# B113X.net
KiCad netlist of a schematic drawn in EAGLE
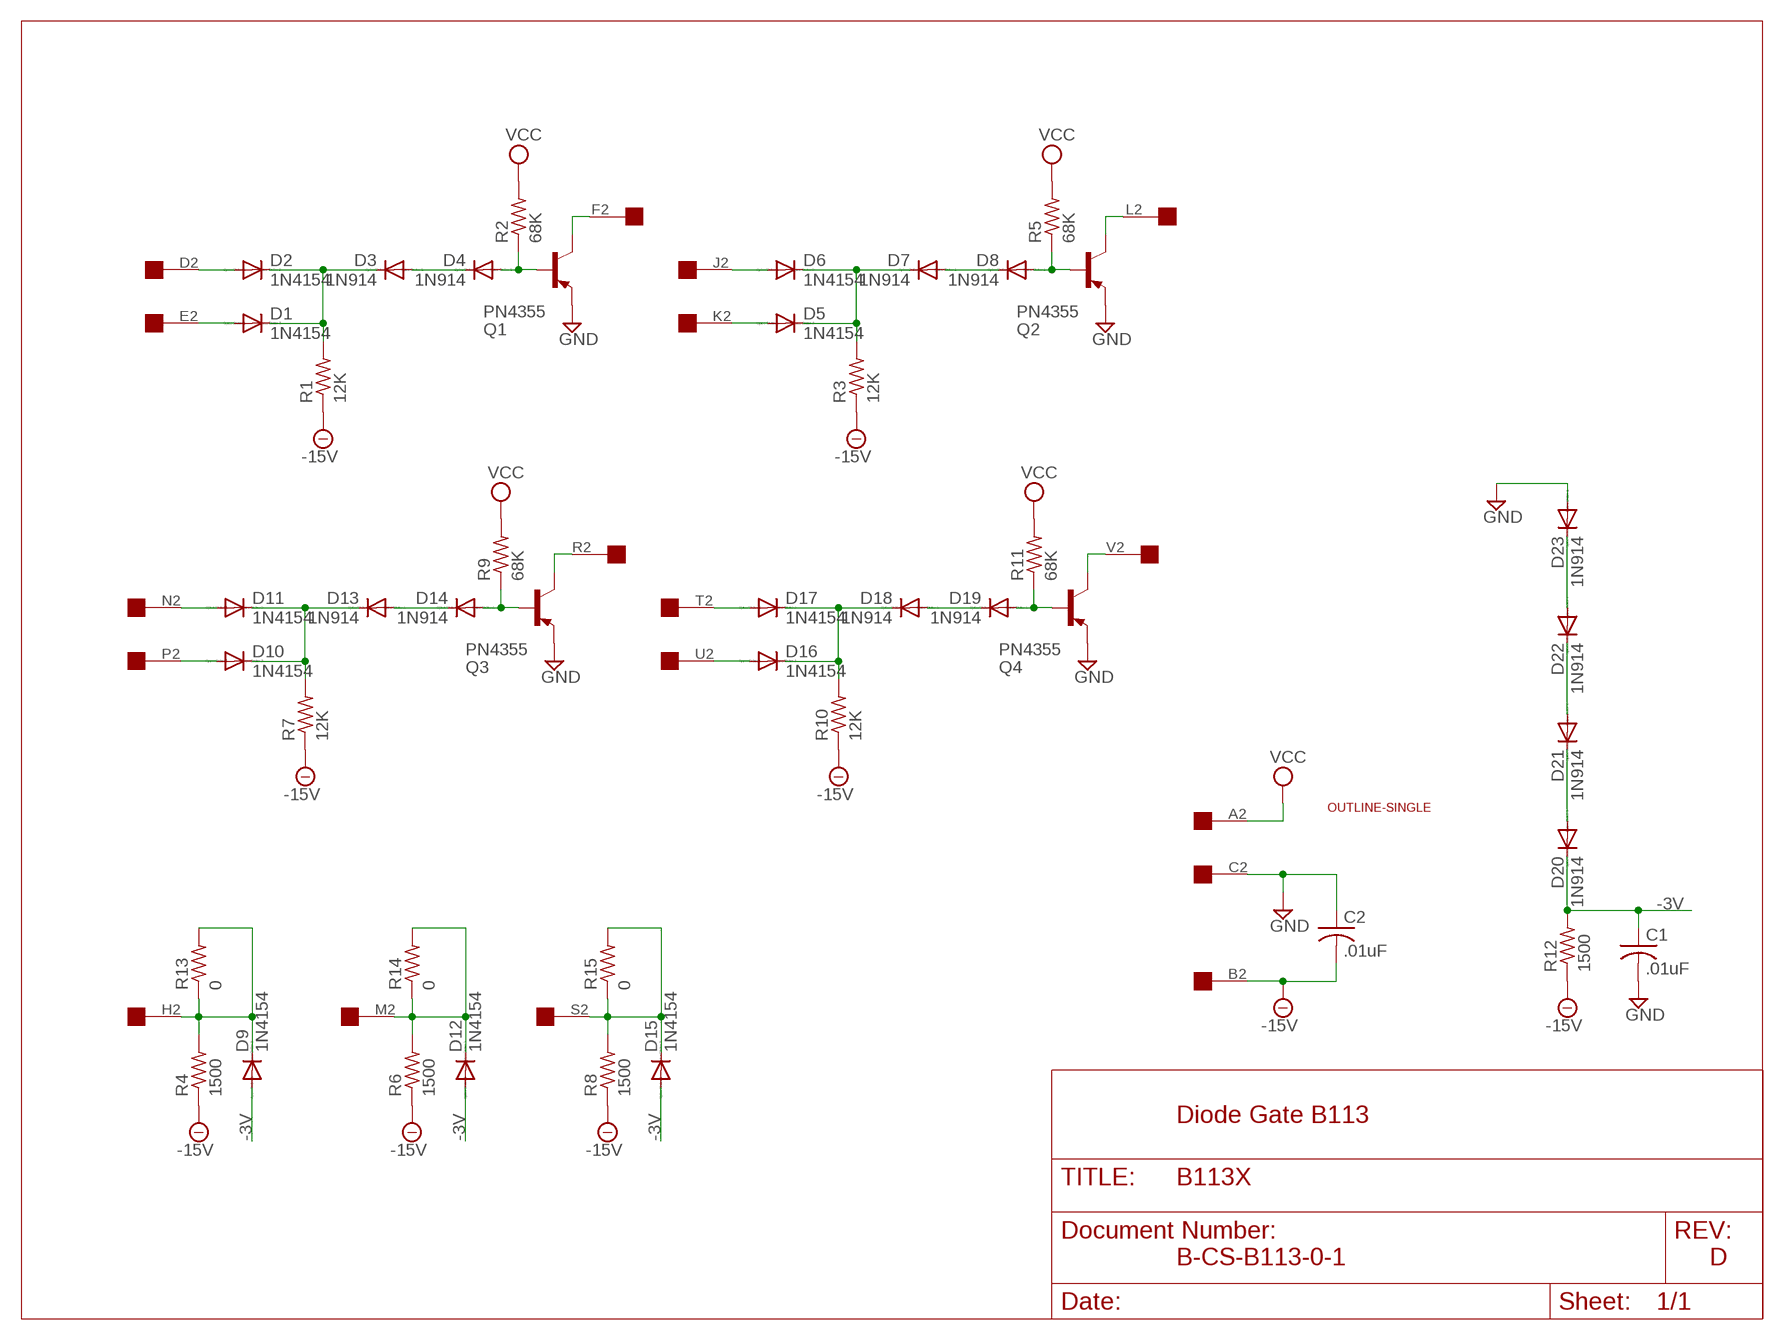
[diagram p0: schematic, sheet 1]

(export (version "E")
  (design (tool "Eeschema 10.0.6"))
  (components
    (comp (ref "C1")
      (value ".01uF")
      (footprint "eagle-import:C063-025X075")
      (libsource (lib "eagle-import") (part "C-US"))
    )
    (comp (ref "C2")
      (value ".01uF")
      (footprint "eagle-import:C063-025X075")
      (libsource (lib "eagle-import") (part "C-US"))
    )
    (comp (ref "D1")
      (value "1N4154")
      (footprint "eagle-import:DO35-10")
      (libsource (lib "eagle-import") (part "DIODE-DO35-10"))
    )
    (comp (ref "D2")
      (value "1N4154")
      (footprint "eagle-import:DO35-10")
      (libsource (lib "eagle-import") (part "DIODE-DO35-10"))
    )
    (comp (ref "D3")
      (value "1N914")
      (footprint "eagle-import:DO35-10")
      (libsource (lib "eagle-import") (part "DIODE-DO35-10"))
    )
    (comp (ref "D4")
      (value "1N914")
      (footprint "eagle-import:DO35-10")
      (libsource (lib "eagle-import") (part "DIODE-DO35-10"))
    )
    (comp (ref "D5")
      (value "1N4154")
      (footprint "eagle-import:DO35-10")
      (libsource (lib "eagle-import") (part "DIODE-DO35-10"))
    )
    (comp (ref "D6")
      (value "1N4154")
      (footprint "eagle-import:DO35-10")
      (libsource (lib "eagle-import") (part "DIODE-DO35-10"))
    )
    (comp (ref "D7")
      (value "1N914")
      (footprint "eagle-import:DO35-10")
      (libsource (lib "eagle-import") (part "DIODE-DO35-10"))
    )
    (comp (ref "D8")
      (value "1N914")
      (footprint "eagle-import:DO35-10")
      (libsource (lib "eagle-import") (part "DIODE-DO35-10"))
    )
    (comp (ref "D9")
      (value "1N4154")
      (footprint "eagle-import:DO35-10")
      (libsource (lib "eagle-import") (part "DIODE-DO35-10"))
    )
    (comp (ref "D10")
      (value "1N4154")
      (footprint "eagle-import:DO35-10")
      (libsource (lib "eagle-import") (part "DIODE-DO35-10"))
    )
    (comp (ref "D11")
      (value "1N4154")
      (footprint "eagle-import:DO35-10")
      (libsource (lib "eagle-import") (part "DIODE-DO35-10"))
    )
    (comp (ref "D12")
      (value "1N4154")
      (footprint "eagle-import:DO35-10")
      (libsource (lib "eagle-import") (part "DIODE-DO35-10"))
    )
    (comp (ref "D13")
      (value "1N914")
      (footprint "eagle-import:DO35-10")
      (libsource (lib "eagle-import") (part "DIODE-DO35-10"))
    )
    (comp (ref "D14")
      (value "1N914")
      (footprint "eagle-import:DO35-10")
      (libsource (lib "eagle-import") (part "DIODE-DO35-10"))
    )
    (comp (ref "D15")
      (value "1N4154")
      (footprint "eagle-import:DO35-10")
      (libsource (lib "eagle-import") (part "DIODE-DO35-10"))
    )
    (comp (ref "D16")
      (value "1N4154")
      (footprint "eagle-import:DO35-10")
      (libsource (lib "eagle-import") (part "DIODE-DO35-10"))
    )
    (comp (ref "D17")
      (value "1N4154")
      (footprint "eagle-import:DO35-10")
      (libsource (lib "eagle-import") (part "DIODE-DO35-10"))
    )
    (comp (ref "D18")
      (value "1N914")
      (footprint "eagle-import:DO35-10")
      (libsource (lib "eagle-import") (part "DIODE-DO35-10"))
    )
    (comp (ref "D19")
      (value "1N914")
      (footprint "eagle-import:DO35-10")
      (libsource (lib "eagle-import") (part "DIODE-DO35-10"))
    )
    (comp (ref "D20")
      (value "1N914")
      (footprint "eagle-import:DO35-10")
      (libsource (lib "eagle-import") (part "DIODE-DO35-10"))
    )
    (comp (ref "D21")
      (value "1N914")
      (footprint "eagle-import:DO35-10")
      (libsource (lib "eagle-import") (part "DIODE-DO35-10"))
    )
    (comp (ref "D22")
      (value "1N914")
      (footprint "eagle-import:DO35-10")
      (libsource (lib "eagle-import") (part "DIODE-DO35-10"))
    )
    (comp (ref "D23")
      (value "1N914")
      (footprint "eagle-import:DO35-10")
      (libsource (lib "eagle-import") (part "DIODE-DO35-10"))
    )
    (comp (ref "Q1")
      (value "PN4355")
      (footprint "eagle-import:TO5")
      (libsource (lib "eagle-import") (part "-PNP-TO5"))
    )
    (comp (ref "Q2")
      (value "PN4355")
      (footprint "eagle-import:TO5")
      (libsource (lib "eagle-import") (part "-PNP-TO5"))
    )
    (comp (ref "Q3")
      (value "PN4355")
      (footprint "eagle-import:TO5")
      (libsource (lib "eagle-import") (part "-PNP-TO5"))
    )
    (comp (ref "Q4")
      (value "PN4355")
      (footprint "eagle-import:TO5")
      (libsource (lib "eagle-import") (part "-PNP-TO5"))
    )
    (comp (ref "R1")
      (value "12K")
      (footprint "eagle-import:0207_10")
      (libsource (lib "eagle-import") (part "R-US_0207/10"))
    )
    (comp (ref "R2")
      (value "68K")
      (footprint "eagle-import:0207_10")
      (libsource (lib "eagle-import") (part "R-US_0207/10"))
    )
    (comp (ref "R3")
      (value "12K")
      (footprint "eagle-import:0207_10")
      (libsource (lib "eagle-import") (part "R-US_0207/10"))
    )
    (comp (ref "R4")
      (value "1500")
      (footprint "eagle-import:0207_10")
      (libsource (lib "eagle-import") (part "R-US_0207/10"))
    )
    (comp (ref "R5")
      (value "68K")
      (footprint "eagle-import:0207_10")
      (libsource (lib "eagle-import") (part "R-US_0207/10"))
    )
    (comp (ref "R6")
      (value "1500")
      (footprint "eagle-import:0207_10")
      (libsource (lib "eagle-import") (part "R-US_0207/10"))
    )
    (comp (ref "R7")
      (value "12K")
      (footprint "eagle-import:0207_10")
      (libsource (lib "eagle-import") (part "R-US_0207/10"))
    )
    (comp (ref "R8")
      (value "1500")
      (footprint "eagle-import:0207_10")
      (libsource (lib "eagle-import") (part "R-US_0207/10"))
    )
    (comp (ref "R9")
      (value "68K")
      (footprint "eagle-import:0207_10")
      (libsource (lib "eagle-import") (part "R-US_0207/10"))
    )
    (comp (ref "R10")
      (value "12K")
      (footprint "eagle-import:0207_10")
      (libsource (lib "eagle-import") (part "R-US_0207/10"))
    )
    (comp (ref "R11")
      (value "68K")
      (footprint "eagle-import:0207_10")
      (libsource (lib "eagle-import") (part "R-US_0207/10"))
    )
    (comp (ref "R12")
      (value "1500")
      (footprint "eagle-import:0207_10")
      (libsource (lib "eagle-import") (part "R-US_0207/10"))
    )
    (comp (ref "R13")
      (value "0")
      (footprint "eagle-import:0207_10")
      (libsource (lib "eagle-import") (part "R-US_0207/10"))
    )
    (comp (ref "R14")
      (value "0")
      (footprint "eagle-import:0207_10")
      (libsource (lib "eagle-import") (part "R-US_0207/10"))
    )
    (comp (ref "R15")
      (value "0")
      (footprint "eagle-import:0207_10")
      (libsource (lib "eagle-import") (part "R-US_0207/10"))
    )
    (comp (ref "U$1")
      (value "OUTLINE-SINGLE")
      (footprint "eagle-import:SINGLE")
      (libsource (lib "eagle-import") (part "OUTLINE-SINGLE"))
    )
    (comp (ref "U$2")
      (value "EDGE-1")
      (footprint "eagle-import:EDGE-CON1")
      (libsource (lib "eagle-import") (part "EDGE-1"))
    )
  )
  (nets
    (net (code "1") (name "-15V") (class "Default")
      (node (ref "C2") (pin "2") (pinfunction "2_2") (pintype "passive"))
      (node (ref "R1") (pin "1") (pinfunction "1_1") (pintype "passive"))
      (node (ref "R10") (pin "1") (pinfunction "1_1") (pintype "passive"))
      (node (ref "R12") (pin "1") (pinfunction "1_1") (pintype "passive"))
      (node (ref "R3") (pin "1") (pinfunction "1_1") (pintype "passive"))
      (node (ref "R4") (pin "1") (pinfunction "1_1") (pintype "passive"))
      (node (ref "R6") (pin "1") (pinfunction "1_1") (pintype "passive"))
      (node (ref "R7") (pin "1") (pinfunction "1_1") (pintype "passive"))
      (node (ref "R8") (pin "1") (pinfunction "1_1") (pintype "passive"))
      (node (ref "U$2") (pin "B2") (pinfunction "1_B2") (pintype "bidirectional"))
    )
    (net (code "2") (name "/-3V") (class "Default")
      (node (ref "C1") (pin "1") (pinfunction "1_1") (pintype "passive"))
      (node (ref "D12") (pin "A") (pinfunction "A_A") (pintype "passive"))
      (node (ref "D15") (pin "A") (pinfunction "A_A") (pintype "passive"))
      (node (ref "D20") (pin "C") (pinfunction "C_C") (pintype "passive"))
      (node (ref "D9") (pin "A") (pinfunction "A_A") (pintype "passive"))
      (node (ref "R12") (pin "2") (pinfunction "2_2") (pintype "passive"))
    )
    (net (code "3") (name "GND") (class "Default")
      (node (ref "C1") (pin "2") (pinfunction "2_2") (pintype "passive"))
      (node (ref "C2") (pin "1") (pinfunction "1_1") (pintype "passive"))
      (node (ref "D23") (pin "A") (pinfunction "A_A") (pintype "passive"))
      (node (ref "Q1") (pin "1") (pinfunction "E_1") (pintype "passive"))
      (node (ref "Q2") (pin "1") (pinfunction "E_1") (pintype "passive"))
      (node (ref "Q3") (pin "1") (pinfunction "E_1") (pintype "passive"))
      (node (ref "Q4") (pin "1") (pinfunction "E_1") (pintype "passive"))
      (node (ref "U$2") (pin "C2") (pinfunction "1_C2") (pintype "bidirectional"))
    )
    (net (code "4") (name "Net-(D1-PadC)") (class "Default")
      (node (ref "D1") (pin "C") (pinfunction "C_C") (pintype "passive"))
      (node (ref "D2") (pin "C") (pinfunction "C_C") (pintype "passive"))
      (node (ref "D3") (pin "C") (pinfunction "C_C") (pintype "passive"))
      (node (ref "R1") (pin "2") (pinfunction "2_2") (pintype "passive"))
    )
    (net (code "5") (name "Net-(D3-PadA)") (class "Default")
      (node (ref "D3") (pin "A") (pinfunction "A_A") (pintype "passive"))
      (node (ref "D4") (pin "C") (pinfunction "C_C") (pintype "passive"))
    )
    (net (code "6") (name "Net-(D5-PadC)") (class "Default")
      (node (ref "D5") (pin "C") (pinfunction "C_C") (pintype "passive"))
      (node (ref "D6") (pin "C") (pinfunction "C_C") (pintype "passive"))
      (node (ref "D7") (pin "C") (pinfunction "C_C") (pintype "passive"))
      (node (ref "R3") (pin "2") (pinfunction "2_2") (pintype "passive"))
    )
    (net (code "7") (name "Net-(D7-PadA)") (class "Default")
      (node (ref "D7") (pin "A") (pinfunction "A_A") (pintype "passive"))
      (node (ref "D8") (pin "C") (pinfunction "C_C") (pintype "passive"))
    )
    (net (code "8") (name "Net-(D10-PadC)") (class "Default")
      (node (ref "D10") (pin "C") (pinfunction "C_C") (pintype "passive"))
      (node (ref "D11") (pin "C") (pinfunction "C_C") (pintype "passive"))
      (node (ref "D13") (pin "C") (pinfunction "C_C") (pintype "passive"))
      (node (ref "R7") (pin "2") (pinfunction "2_2") (pintype "passive"))
    )
    (net (code "9") (name "Net-(D13-PadA)") (class "Default")
      (node (ref "D13") (pin "A") (pinfunction "A_A") (pintype "passive"))
      (node (ref "D14") (pin "C") (pinfunction "C_C") (pintype "passive"))
    )
    (net (code "10") (name "Net-(D16-PadC)") (class "Default")
      (node (ref "D16") (pin "C") (pinfunction "C_C") (pintype "passive"))
      (node (ref "D17") (pin "C") (pinfunction "C_C") (pintype "passive"))
      (node (ref "D18") (pin "C") (pinfunction "C_C") (pintype "passive"))
      (node (ref "R10") (pin "2") (pinfunction "2_2") (pintype "passive"))
    )
    (net (code "11") (name "Net-(D18-PadA)") (class "Default")
      (node (ref "D18") (pin "A") (pinfunction "A_A") (pintype "passive"))
      (node (ref "D19") (pin "C") (pinfunction "C_C") (pintype "passive"))
    )
    (net (code "12") (name "Net-(D20-PadA)") (class "Default")
      (node (ref "D20") (pin "A") (pinfunction "A_A") (pintype "passive"))
      (node (ref "D21") (pin "C") (pinfunction "C_C") (pintype "passive"))
    )
    (net (code "13") (name "Net-(D21-PadA)") (class "Default")
      (node (ref "D21") (pin "A") (pinfunction "A_A") (pintype "passive"))
      (node (ref "D22") (pin "C") (pinfunction "C_C") (pintype "passive"))
    )
    (net (code "14") (name "Net-(D22-PadA)") (class "Default")
      (node (ref "D22") (pin "A") (pinfunction "A_A") (pintype "passive"))
      (node (ref "D23") (pin "C") (pinfunction "C_C") (pintype "passive"))
    )
    (net (code "15") (name "Net-(Q1-B)") (class "Default")
      (node (ref "D4") (pin "A") (pinfunction "A_A") (pintype "passive"))
      (node (ref "Q1") (pin "2") (pinfunction "B_2") (pintype "passive"))
      (node (ref "R2") (pin "1") (pinfunction "1_1") (pintype "passive"))
    )
    (net (code "16") (name "Net-(Q1-C)") (class "Default")
      (node (ref "Q1") (pin "3") (pinfunction "C_3") (pintype "passive"))
      (node (ref "U$2") (pin "F2") (pinfunction "1_F2") (pintype "bidirectional"))
    )
    (net (code "17") (name "Net-(Q2-B)") (class "Default")
      (node (ref "D8") (pin "A") (pinfunction "A_A") (pintype "passive"))
      (node (ref "Q2") (pin "2") (pinfunction "B_2") (pintype "passive"))
      (node (ref "R5") (pin "1") (pinfunction "1_1") (pintype "passive"))
    )
    (net (code "18") (name "Net-(Q2-C)") (class "Default")
      (node (ref "Q2") (pin "3") (pinfunction "C_3") (pintype "passive"))
      (node (ref "U$2") (pin "L2") (pinfunction "1_L2") (pintype "bidirectional"))
    )
    (net (code "19") (name "Net-(Q3-B)") (class "Default")
      (node (ref "D14") (pin "A") (pinfunction "A_A") (pintype "passive"))
      (node (ref "Q3") (pin "2") (pinfunction "B_2") (pintype "passive"))
      (node (ref "R9") (pin "1") (pinfunction "1_1") (pintype "passive"))
    )
    (net (code "20") (name "Net-(Q3-C)") (class "Default")
      (node (ref "Q3") (pin "3") (pinfunction "C_3") (pintype "passive"))
      (node (ref "U$2") (pin "R2") (pinfunction "1_R2") (pintype "bidirectional"))
    )
    (net (code "21") (name "Net-(Q4-B)") (class "Default")
      (node (ref "D19") (pin "A") (pinfunction "A_A") (pintype "passive"))
      (node (ref "Q4") (pin "2") (pinfunction "B_2") (pintype "passive"))
      (node (ref "R11") (pin "1") (pinfunction "1_1") (pintype "passive"))
    )
    (net (code "22") (name "Net-(Q4-C)") (class "Default")
      (node (ref "Q4") (pin "3") (pinfunction "C_3") (pintype "passive"))
      (node (ref "U$2") (pin "V2") (pinfunction "1_V2") (pintype "bidirectional"))
    )
    (net (code "23") (name "Net-(U$2D-1)") (class "Default")
      (node (ref "D2") (pin "A") (pinfunction "A_A") (pintype "passive"))
      (node (ref "U$2") (pin "D2") (pinfunction "1_D2") (pintype "bidirectional"))
    )
    (net (code "24") (name "Net-(U$2E-1)") (class "Default")
      (node (ref "D1") (pin "A") (pinfunction "A_A") (pintype "passive"))
      (node (ref "U$2") (pin "E2") (pinfunction "1_E2") (pintype "bidirectional"))
    )
    (net (code "25") (name "Net-(U$2G-1)") (class "Default")
      (node (ref "D9") (pin "C") (pinfunction "C_C") (pintype "passive"))
      (node (ref "R13") (pin "1") (pinfunction "1_1") (pintype "passive"))
      (node (ref "R13") (pin "2") (pinfunction "2_2") (pintype "passive"))
      (node (ref "R4") (pin "2") (pinfunction "2_2") (pintype "passive"))
      (node (ref "U$2") (pin "H2") (pinfunction "1_H2") (pintype "bidirectional"))
    )
    (net (code "26") (name "Net-(U$2H-1)") (class "Default")
      (node (ref "D6") (pin "A") (pinfunction "A_A") (pintype "passive"))
      (node (ref "U$2") (pin "J2") (pinfunction "1_J2") (pintype "bidirectional"))
    )
    (net (code "27") (name "Net-(U$2I-1)") (class "Default")
      (node (ref "D5") (pin "A") (pinfunction "A_A") (pintype "passive"))
      (node (ref "U$2") (pin "K2") (pinfunction "1_K2") (pintype "bidirectional"))
    )
    (net (code "28") (name "Net-(U$2K-1)") (class "Default")
      (node (ref "D12") (pin "C") (pinfunction "C_C") (pintype "passive"))
      (node (ref "R14") (pin "1") (pinfunction "1_1") (pintype "passive"))
      (node (ref "R14") (pin "2") (pinfunction "2_2") (pintype "passive"))
      (node (ref "R6") (pin "2") (pinfunction "2_2") (pintype "passive"))
      (node (ref "U$2") (pin "M2") (pinfunction "1_M2") (pintype "bidirectional"))
    )
    (net (code "29") (name "Net-(U$2L-1)") (class "Default")
      (node (ref "D11") (pin "A") (pinfunction "A_A") (pintype "passive"))
      (node (ref "U$2") (pin "N2") (pinfunction "1_N2") (pintype "bidirectional"))
    )
    (net (code "30") (name "Net-(U$2M-1)") (class "Default")
      (node (ref "D10") (pin "A") (pinfunction "A_A") (pintype "passive"))
      (node (ref "U$2") (pin "P2") (pinfunction "1_P2") (pintype "bidirectional"))
    )
    (net (code "31") (name "Net-(U$2O-1)") (class "Default")
      (node (ref "D15") (pin "C") (pinfunction "C_C") (pintype "passive"))
      (node (ref "R15") (pin "1") (pinfunction "1_1") (pintype "passive"))
      (node (ref "R15") (pin "2") (pinfunction "2_2") (pintype "passive"))
      (node (ref "R8") (pin "2") (pinfunction "2_2") (pintype "passive"))
      (node (ref "U$2") (pin "S2") (pinfunction "1_S2") (pintype "bidirectional"))
    )
    (net (code "32") (name "Net-(U$2P-1)") (class "Default")
      (node (ref "D17") (pin "A") (pinfunction "A_A") (pintype "passive"))
      (node (ref "U$2") (pin "T2") (pinfunction "1_T2") (pintype "bidirectional"))
    )
    (net (code "33") (name "Net-(U$2Q-1)") (class "Default")
      (node (ref "D16") (pin "A") (pinfunction "A_A") (pintype "passive"))
      (node (ref "U$2") (pin "U2") (pinfunction "1_U2") (pintype "bidirectional"))
    )
    (net (code "34") (name "VCC") (class "Default")
      (node (ref "R11") (pin "2") (pinfunction "2_2") (pintype "passive"))
      (node (ref "R2") (pin "2") (pinfunction "2_2") (pintype "passive"))
      (node (ref "R5") (pin "2") (pinfunction "2_2") (pintype "passive"))
      (node (ref "R9") (pin "2") (pinfunction "2_2") (pintype "passive"))
      (node (ref "U$2") (pin "A2") (pinfunction "1_A2") (pintype "bidirectional"))
    )
  )
)
